# Arduino_Ibus.net
KiCad netlist of a schematic drawn in EAGLE
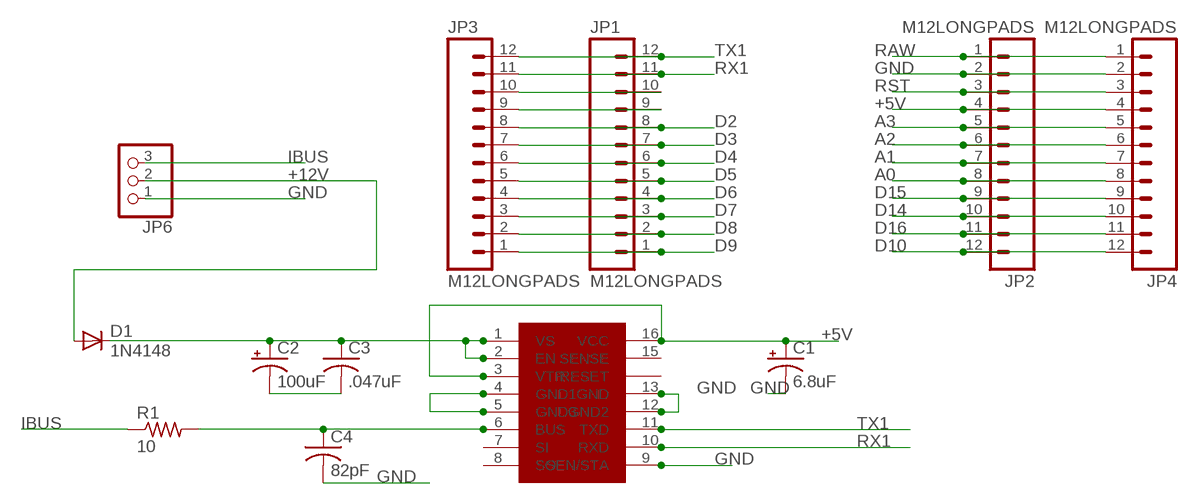
[diagram p0: schematic, sheet 1]

(export (version "E")
  (design (tool "Eeschema 10.0.6"))
  (components
    (comp (ref "C1")
      (value "6.8uF")
      (footprint "eagle-import:E1,8-4")
      (libsource (lib "eagle-import") (part "CPOL-USE1.8-4"))
    )
    (comp (ref "C2")
      (value "100uF")
      (footprint "eagle-import:E3,5-8")
      (libsource (lib "eagle-import") (part "CPOL-USE3.5-8"))
    )
    (comp (ref "C3")
      (value ".047uF")
      (footprint "eagle-import:C050-030X075")
      (libsource (lib "eagle-import") (part "C-US050-030X075"))
    )
    (comp (ref "C4")
      (value "82pF")
      (footprint "eagle-import:C050-030X075")
      (libsource (lib "eagle-import") (part "C-US050-030X075"))
    )
    (comp (ref "D1")
      (value "1N4148")
      (footprint "eagle-import:DO35-7")
      (libsource (lib "eagle-import") (part "1N4148DO35-7"))
    )
    (comp (ref "JP1")
      (value "M12LONGPADS")
      (footprint "eagle-import:1X12_LONGPADS")
      (libsource (lib "eagle-import") (part "M12LONGPADS"))
    )
    (comp (ref "JP2")
      (value "M12LONGPADS")
      (footprint "eagle-import:1X12_LONGPADS")
      (libsource (lib "eagle-import") (part "M12LONGPADS"))
    )
    (comp (ref "JP3")
      (value "M12LONGPADS")
      (footprint "eagle-import:1X12_LONGPADS")
      (libsource (lib "eagle-import") (part "M12LONGPADS"))
    )
    (comp (ref "JP4")
      (value "M12LONGPADS")
      (footprint "eagle-import:1X12_LONGPADS")
      (libsource (lib "eagle-import") (part "M12LONGPADS"))
    )
    (comp (ref "JP6")
      (value "PINHD-1X3")
      (footprint "eagle-import:1X03")
      (libsource (lib "eagle-import") (part "PINHD-1X3"))
    )
    (comp (ref "R1")
      (value "10")
      (footprint "eagle-import:0207_7")
      (libsource (lib "eagle-import") (part "R-US_0207/7"))
    )
    (comp (ref "U$1")
      (value "TH3122")
      (footprint "eagle-import:SO16W")
      (libsource (lib "eagle-import") (part "TH3122"))
    )
  )
  (nets
    (net (code "1") (name "/+5V") (class "Default")
      (node (ref "C1") (pin "+") (pinfunction "+_+") (pintype "passive"))
      (node (ref "JP2") (pin "4") (pinfunction "4_4") (pintype "passive"))
      (node (ref "JP4") (pin "4") (pinfunction "4_4") (pintype "passive"))
      (node (ref "U$1") (pin "16") (pinfunction "VCC_16") (pintype "power_in"))
      (node (ref "U$1") (pin "3") (pinfunction "VTR_3") (pintype "bidirectional"))
    )
    (net (code "2") (name "/+12V") (class "Default")
      (node (ref "D1") (pin "A") (pinfunction "A_A") (pintype "passive"))
      (node (ref "JP6") (pin "2") (pinfunction "2_2") (pintype "passive"))
    )
    (net (code "3") (name "/A0") (class "Default")
      (node (ref "JP2") (pin "8") (pinfunction "8_8") (pintype "passive"))
      (node (ref "JP4") (pin "8") (pinfunction "8_8") (pintype "passive"))
    )
    (net (code "4") (name "/A1") (class "Default")
      (node (ref "JP2") (pin "7") (pinfunction "7_7") (pintype "passive"))
      (node (ref "JP4") (pin "7") (pinfunction "7_7") (pintype "passive"))
    )
    (net (code "5") (name "/A2") (class "Default")
      (node (ref "JP2") (pin "6") (pinfunction "6_6") (pintype "passive"))
      (node (ref "JP4") (pin "6") (pinfunction "6_6") (pintype "passive"))
    )
    (net (code "6") (name "/A3") (class "Default")
      (node (ref "JP2") (pin "5") (pinfunction "5_5") (pintype "passive"))
      (node (ref "JP4") (pin "5") (pinfunction "5_5") (pintype "passive"))
    )
    (net (code "7") (name "/D2") (class "Default")
      (node (ref "JP1") (pin "8") (pinfunction "8_8") (pintype "passive"))
      (node (ref "JP3") (pin "8") (pinfunction "8_8") (pintype "passive"))
    )
    (net (code "8") (name "/D3") (class "Default")
      (node (ref "JP1") (pin "7") (pinfunction "7_7") (pintype "passive"))
      (node (ref "JP3") (pin "7") (pinfunction "7_7") (pintype "passive"))
    )
    (net (code "9") (name "/D4") (class "Default")
      (node (ref "JP1") (pin "6") (pinfunction "6_6") (pintype "passive"))
      (node (ref "JP3") (pin "6") (pinfunction "6_6") (pintype "passive"))
    )
    (net (code "10") (name "/D5") (class "Default")
      (node (ref "JP1") (pin "5") (pinfunction "5_5") (pintype "passive"))
      (node (ref "JP3") (pin "5") (pinfunction "5_5") (pintype "passive"))
    )
    (net (code "11") (name "/D6") (class "Default")
      (node (ref "JP1") (pin "4") (pinfunction "4_4") (pintype "passive"))
      (node (ref "JP3") (pin "4") (pinfunction "4_4") (pintype "passive"))
    )
    (net (code "12") (name "/D7") (class "Default")
      (node (ref "JP1") (pin "3") (pinfunction "3_3") (pintype "passive"))
      (node (ref "JP3") (pin "3") (pinfunction "3_3") (pintype "passive"))
    )
    (net (code "13") (name "/D8") (class "Default")
      (node (ref "JP1") (pin "2") (pinfunction "2_2") (pintype "passive"))
      (node (ref "JP3") (pin "2") (pinfunction "2_2") (pintype "passive"))
    )
    (net (code "14") (name "/D9") (class "Default")
      (node (ref "JP1") (pin "1") (pinfunction "1_1") (pintype "passive"))
      (node (ref "JP3") (pin "1") (pinfunction "1_1") (pintype "passive"))
    )
    (net (code "15") (name "/D10") (class "Default")
      (node (ref "JP2") (pin "12") (pinfunction "12_12") (pintype "passive"))
      (node (ref "JP4") (pin "12") (pinfunction "12_12") (pintype "passive"))
    )
    (net (code "16") (name "/D14") (class "Default")
      (node (ref "JP2") (pin "10") (pinfunction "10_10") (pintype "passive"))
      (node (ref "JP4") (pin "10") (pinfunction "10_10") (pintype "passive"))
    )
    (net (code "17") (name "/D15") (class "Default")
      (node (ref "JP2") (pin "9") (pinfunction "9_9") (pintype "passive"))
      (node (ref "JP4") (pin "9") (pinfunction "9_9") (pintype "passive"))
    )
    (net (code "18") (name "/D16") (class "Default")
      (node (ref "JP2") (pin "11") (pinfunction "11_11") (pintype "passive"))
      (node (ref "JP4") (pin "11") (pinfunction "11_11") (pintype "passive"))
    )
    (net (code "19") (name "/GND") (class "Default")
      (node (ref "C1") (pin "-") (pinfunction "-_-") (pintype "passive"))
      (node (ref "C2") (pin "-") (pinfunction "-_-") (pintype "passive"))
      (node (ref "C3") (pin "2") (pinfunction "2_2") (pintype "passive"))
      (node (ref "C4") (pin "2") (pinfunction "2_2") (pintype "passive"))
      (node (ref "JP2") (pin "2") (pinfunction "2_2") (pintype "passive"))
      (node (ref "JP4") (pin "2") (pinfunction "2_2") (pintype "passive"))
      (node (ref "JP6") (pin "1") (pinfunction "1_1") (pintype "passive"))
      (node (ref "U$1") (pin "12") (pinfunction "GND2_12") (pintype "power_in"))
      (node (ref "U$1") (pin "13") (pinfunction "GND_13") (pintype "power_in"))
      (node (ref "U$1") (pin "4") (pinfunction "GND1_4") (pintype "power_in"))
      (node (ref "U$1") (pin "5") (pinfunction "GND3_5") (pintype "power_in"))
      (node (ref "U$1") (pin "9") (pinfunction "SEN/STA_9") (pintype "bidirectional"))
    )
    (net (code "20") (name "/IBUS") (class "Default")
      (node (ref "JP6") (pin "3") (pinfunction "3_3") (pintype "passive"))
      (node (ref "R1") (pin "1") (pinfunction "1_1") (pintype "passive"))
    )
    (net (code "21") (name "/RAW") (class "Default")
      (node (ref "JP2") (pin "1") (pinfunction "1_1") (pintype "passive"))
      (node (ref "JP4") (pin "1") (pinfunction "1_1") (pintype "passive"))
    )
    (net (code "22") (name "/RST") (class "Default")
      (node (ref "JP2") (pin "3") (pinfunction "3_3") (pintype "passive"))
      (node (ref "JP4") (pin "3") (pinfunction "3_3") (pintype "passive"))
    )
    (net (code "23") (name "/RX1") (class "Default")
      (node (ref "JP1") (pin "11") (pinfunction "11_11") (pintype "passive"))
      (node (ref "JP3") (pin "11") (pinfunction "11_11") (pintype "passive"))
      (node (ref "U$1") (pin "10") (pinfunction "RXD_10") (pintype "input"))
    )
    (net (code "24") (name "/TX1") (class "Default")
      (node (ref "JP1") (pin "12") (pinfunction "12_12") (pintype "passive"))
      (node (ref "JP3") (pin "12") (pinfunction "12_12") (pintype "passive"))
      (node (ref "U$1") (pin "11") (pinfunction "TXD_11") (pintype "output"))
    )
    (net (code "25") (name "Net-(JP1-Pad9)") (class "Default")
      (node (ref "JP1") (pin "9") (pinfunction "9_9") (pintype "passive"))
      (node (ref "JP3") (pin "9") (pinfunction "9_9") (pintype "passive"))
    )
    (net (code "26") (name "Net-(JP1-Pad10)") (class "Default")
      (node (ref "JP1") (pin "10") (pinfunction "10_10") (pintype "passive"))
      (node (ref "JP3") (pin "10") (pinfunction "10_10") (pintype "passive"))
    )
    (net (code "27") (name "Net-(U$1-BUS)") (class "Default")
      (node (ref "C4") (pin "1") (pinfunction "1_1") (pintype "passive"))
      (node (ref "R1") (pin "2") (pinfunction "2_2") (pintype "passive"))
      (node (ref "U$1") (pin "6") (pinfunction "BUS_6") (pintype "bidirectional"))
    )
    (net (code "28") (name "Net-(U$1-EN)") (class "Default")
      (node (ref "C2") (pin "+") (pinfunction "+_+") (pintype "passive"))
      (node (ref "C3") (pin "1") (pinfunction "1_1") (pintype "passive"))
      (node (ref "D1") (pin "C") (pinfunction "C_C") (pintype "passive"))
      (node (ref "U$1") (pin "1") (pinfunction "VS_1") (pintype "power_in"))
      (node (ref "U$1") (pin "2") (pinfunction "EN_2") (pintype "bidirectional"))
    )
    (net (code "29") (name "unconnected-(U$1-RESET-Pad14)") (class "Default")
      (node (ref "U$1") (pin "14") (pinfunction "RESET_14") (pintype "bidirectional"))
    )
    (net (code "30") (name "unconnected-(U$1-SENSE-Pad15)") (class "Default")
      (node (ref "U$1") (pin "15") (pinfunction "SENSE_15") (pintype "bidirectional"))
    )
    (net (code "31") (name "unconnected-(U$1-SI-Pad7)") (class "Default")
      (node (ref "U$1") (pin "7") (pinfunction "SI_7") (pintype "bidirectional"))
    )
    (net (code "32") (name "unconnected-(U$1-SO-Pad8)") (class "Default")
      (node (ref "U$1") (pin "8") (pinfunction "SO_8") (pintype "bidirectional"))
    )
  )
)
